# untitled.net
KiCad netlist of a schematic drawn in EAGLE
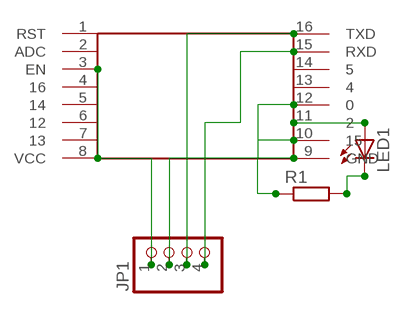
[diagram p0: schematic, sheet 1]

(export (version "E")
  (design (tool "Eeschema 10.0.6"))
  (components
    (comp (ref "JP1")
      (value "PINHD-1X4")
      (footprint "eagle-import:1X04")
      (libsource (lib "eagle-import") (part "PINHD-1X4"))
    )
    (comp (ref "LED1")
      (value "LED3MM")
      (footprint "eagle-import:LED3MM")
      (libsource (lib "eagle-import") (part "LED3MM"))
    )
    (comp (ref "R1")
      (value "R-EU_0204/2V")
      (footprint "eagle-import:0204V")
      (libsource (lib "eagle-import") (part "R-EU_0204/2V"))
    )
    (comp (ref "U$1")
      (value "ESP8266-12E")
      (footprint "eagle-import:ESP")
      (libsource (lib "eagle-import") (part "ESP8266-12E"))
    )
  )
  (nets
    (net (code "1") (name "Net-(LED1-C)") (class "Default")
      (node (ref "LED1") (pin "K") (pinfunction "C_K") (pintype "passive"))
      (node (ref "R1") (pin "2") (pinfunction "2_2") (pintype "passive"))
    )
    (net (code "2") (name "Net-(U$1-0)") (class "Default")
      (node (ref "JP1") (pin "2") (pinfunction "2_2") (pintype "passive"))
      (node (ref "R1") (pin "1") (pinfunction "1_1") (pintype "passive"))
      (node (ref "U$1") (pin "10") (pinfunction "15_10") (pintype "bidirectional"))
      (node (ref "U$1") (pin "12") (pinfunction "0_12") (pintype "bidirectional"))
      (node (ref "U$1") (pin "9") (pinfunction "GND_9") (pintype "bidirectional"))
    )
    (net (code "3") (name "Net-(U$1-2)") (class "Default")
      (node (ref "LED1") (pin "A") (pinfunction "A_A") (pintype "passive"))
      (node (ref "U$1") (pin "11") (pinfunction "2_11") (pintype "bidirectional"))
    )
    (net (code "4") (name "Net-(U$1-EN)") (class "Default")
      (node (ref "JP1") (pin "1") (pinfunction "1_1") (pintype "passive"))
      (node (ref "U$1") (pin "3") (pinfunction "EN_3") (pintype "bidirectional"))
      (node (ref "U$1") (pin "8") (pinfunction "VCC_8") (pintype "bidirectional"))
    )
    (net (code "5") (name "Net-(U$1-RXD)") (class "Default")
      (node (ref "JP1") (pin "4") (pinfunction "4_4") (pintype "passive"))
      (node (ref "U$1") (pin "15") (pinfunction "RXD_15") (pintype "bidirectional"))
    )
    (net (code "6") (name "Net-(U$1-TXD)") (class "Default")
      (node (ref "JP1") (pin "3") (pinfunction "3_3") (pintype "passive"))
      (node (ref "U$1") (pin "16") (pinfunction "TXD_16") (pintype "bidirectional"))
    )
    (net (code "7") (name "unconnected-(U$1-4-Pad13)") (class "Default")
      (node (ref "U$1") (pin "13") (pinfunction "4_13") (pintype "bidirectional"))
    )
    (net (code "8") (name "unconnected-(U$1-5-Pad14)") (class "Default")
      (node (ref "U$1") (pin "14") (pinfunction "5_14") (pintype "bidirectional"))
    )
    (net (code "9") (name "unconnected-(U$1-12-Pad6)") (class "Default")
      (node (ref "U$1") (pin "6") (pinfunction "12_6") (pintype "bidirectional"))
    )
    (net (code "10") (name "unconnected-(U$1-13-Pad7)") (class "Default")
      (node (ref "U$1") (pin "7") (pinfunction "13_7") (pintype "bidirectional"))
    )
    (net (code "11") (name "unconnected-(U$1-14-Pad5)") (class "Default")
      (node (ref "U$1") (pin "5") (pinfunction "14_5") (pintype "bidirectional"))
    )
    (net (code "12") (name "unconnected-(U$1-16-Pad4)") (class "Default")
      (node (ref "U$1") (pin "4") (pinfunction "16_4") (pintype "bidirectional"))
    )
    (net (code "13") (name "unconnected-(U$1-ADC-Pad2)") (class "Default")
      (node (ref "U$1") (pin "2") (pinfunction "ADC_2") (pintype "bidirectional"))
    )
    (net (code "14") (name "unconnected-(U$1-RST-Pad1)") (class "Default")
      (node (ref "U$1") (pin "1") (pinfunction "RST_1") (pintype "bidirectional"))
    )
  )
)
